# BigTimeMain.net
KiCad netlist of a schematic drawn in EAGLE
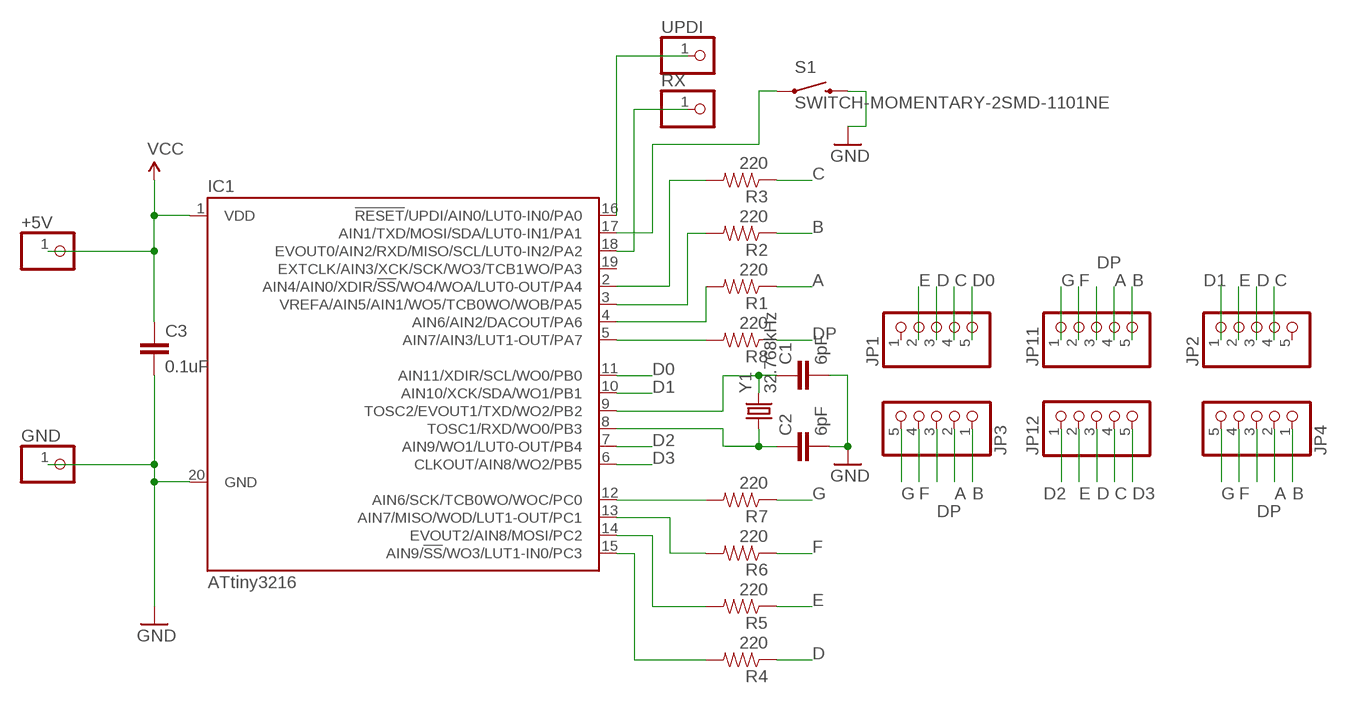
[diagram p0: schematic, sheet 1]

(export (version "E")
  (design (tool "Eeschema 10.0.6"))
  (components
    (comp (ref "+5V")
      (value "PINHD-1X1")
      (footprint "eagle-import:1X01")
      (libsource (lib "eagle-import") (part "PINHD-1X1"))
    )
    (comp (ref "C1")
      (value "6pF")
      (footprint "eagle-import:0805")
      (libsource (lib "eagle-import") (part "CAP0805"))
    )
    (comp (ref "C2")
      (value "6pF")
      (footprint "eagle-import:0805")
      (libsource (lib "eagle-import") (part "CAP0805"))
    )
    (comp (ref "C3")
      (value "0.1uF")
      (footprint "eagle-import:0805")
      (libsource (lib "eagle-import") (part "CAP0805"))
    )
    (comp (ref "GND")
      (value "PINHD-1X1")
      (footprint "eagle-import:1X01")
      (libsource (lib "eagle-import") (part "PINHD-1X1"))
    )
    (comp (ref "IC1")
      (value "ATtiny3216")
      (footprint "eagle-import:SOIC300")
      (fields (field (name "PARTNUM") "ATtiny3216-S*"))
      (libsource (lib "eagle-import") (part "ATTINY1616/3216-S"))
    )
    (comp (ref "JP1")
      (value "HEADER-1X576MIL")
      (footprint "eagle-import:1X05_ROUND_76")
      (libsource (lib "eagle-import") (part "HEADER-1X576MIL"))
    )
    (comp (ref "JP2")
      (value "HEADER-1X576MIL")
      (footprint "eagle-import:1X05_ROUND_76")
      (libsource (lib "eagle-import") (part "HEADER-1X576MIL"))
    )
    (comp (ref "JP3")
      (value "HEADER-1X576MIL")
      (footprint "eagle-import:1X05_ROUND_76")
      (libsource (lib "eagle-import") (part "HEADER-1X576MIL"))
    )
    (comp (ref "JP4")
      (value "HEADER-1X576MIL")
      (footprint "eagle-import:1X05_ROUND_76")
      (libsource (lib "eagle-import") (part "HEADER-1X576MIL"))
    )
    (comp (ref "JP11")
      (value "HEADER-1X576MIL")
      (footprint "eagle-import:1X05_ROUND_76")
      (libsource (lib "eagle-import") (part "HEADER-1X576MIL"))
    )
    (comp (ref "JP12")
      (value "HEADER-1X576MIL")
      (footprint "eagle-import:1X05_ROUND_76")
      (libsource (lib "eagle-import") (part "HEADER-1X576MIL"))
    )
    (comp (ref "R1")
      (value "220")
      (footprint "eagle-import:0805")
      (libsource (lib "eagle-import") (part "0.3OHM-1/8W-1%(0805)"))
    )
    (comp (ref "R2")
      (value "220")
      (footprint "eagle-import:0805")
      (libsource (lib "eagle-import") (part "0.3OHM-1/8W-1%(0805)"))
    )
    (comp (ref "R3")
      (value "220")
      (footprint "eagle-import:0805")
      (libsource (lib "eagle-import") (part "0.3OHM-1/8W-1%(0805)"))
    )
    (comp (ref "R4")
      (value "220")
      (footprint "eagle-import:0805")
      (libsource (lib "eagle-import") (part "0.3OHM-1/8W-1%(0805)"))
    )
    (comp (ref "R5")
      (value "220")
      (footprint "eagle-import:0805")
      (libsource (lib "eagle-import") (part "0.3OHM-1/8W-1%(0805)"))
    )
    (comp (ref "R6")
      (value "220")
      (footprint "eagle-import:0805")
      (libsource (lib "eagle-import") (part "0.3OHM-1/8W-1%(0805)"))
    )
    (comp (ref "R7")
      (value "220")
      (footprint "eagle-import:0805")
      (libsource (lib "eagle-import") (part "0.3OHM-1/8W-1%(0805)"))
    )
    (comp (ref "R8")
      (value "220")
      (footprint "eagle-import:0805")
      (libsource (lib "eagle-import") (part "0.3OHM-1/8W-1%(0805)"))
    )
    (comp (ref "RX")
      (value "PINHD-1X1")
      (footprint "eagle-import:1X01")
      (libsource (lib "eagle-import") (part "PINHD-1X1"))
    )
    (comp (ref "S1")
      (value "SWITCH-MOMENTARY-2SMD-1101NE")
      (footprint "eagle-import:TACTILE-SWITCH-1101NE")
      (libsource (lib "eagle-import") (part "SWITCH-MOMENTARY-2SMD-1101NE"))
    )
    (comp (ref "UPDI")
      (value "PINHD-1X1")
      (footprint "eagle-import:1X01")
      (libsource (lib "eagle-import") (part "PINHD-1X1"))
    )
    (comp (ref "Y1")
      (value "32.768kHz")
      (footprint "eagle-import:CRYSTAL-SMD-3.2X1.5MM")
      (libsource (lib "eagle-import") (part "CRYSTAL3.2X1.5MM"))
    )
  )
  (nets
    (net (code "1") (name "/A") (class "Default")
      (node (ref "JP11") (pin "4") (pinfunction "4_4") (pintype "passive"))
      (node (ref "JP3") (pin "2") (pinfunction "2_2") (pintype "passive"))
      (node (ref "JP4") (pin "2") (pinfunction "2_2") (pintype "passive"))
      (node (ref "R1") (pin "1") (pinfunction "1_1") (pintype "passive"))
    )
    (net (code "2") (name "/B") (class "Default")
      (node (ref "JP11") (pin "5") (pinfunction "5_5") (pintype "passive"))
      (node (ref "JP3") (pin "1") (pinfunction "1_1") (pintype "passive"))
      (node (ref "JP4") (pin "1") (pinfunction "1_1") (pintype "passive"))
      (node (ref "R2") (pin "1") (pinfunction "1_1") (pintype "passive"))
    )
    (net (code "3") (name "/C") (class "Default")
      (node (ref "JP1") (pin "4") (pinfunction "4_4") (pintype "passive"))
      (node (ref "JP12") (pin "4") (pinfunction "4_4") (pintype "passive"))
      (node (ref "JP2") (pin "4") (pinfunction "4_4") (pintype "passive"))
      (node (ref "R3") (pin "1") (pinfunction "1_1") (pintype "passive"))
    )
    (net (code "4") (name "/D") (class "Default")
      (node (ref "JP1") (pin "3") (pinfunction "3_3") (pintype "passive"))
      (node (ref "JP12") (pin "3") (pinfunction "3_3") (pintype "passive"))
      (node (ref "JP2") (pin "3") (pinfunction "3_3") (pintype "passive"))
      (node (ref "R4") (pin "1") (pinfunction "1_1") (pintype "passive"))
    )
    (net (code "5") (name "/D0") (class "Default")
      (node (ref "IC1") (pin "11") (pinfunction "AIN11/XDIR/SCL/WO0/PB0_11") (pintype "passive"))
      (node (ref "JP1") (pin "5") (pinfunction "5_5") (pintype "passive"))
    )
    (net (code "6") (name "/D1") (class "Default")
      (node (ref "IC1") (pin "10") (pinfunction "AIN10/XCK/SDA/WO1/PB1_10") (pintype "passive"))
      (node (ref "JP2") (pin "1") (pinfunction "1_1") (pintype "passive"))
    )
    (net (code "7") (name "/D2") (class "Default")
      (node (ref "IC1") (pin "7") (pinfunction "AIN9/WO1/LUT0-OUT/PB4_7") (pintype "passive"))
      (node (ref "JP12") (pin "1") (pinfunction "1_1") (pintype "passive"))
    )
    (net (code "8") (name "/D3") (class "Default")
      (node (ref "IC1") (pin "6") (pinfunction "CLKOUT/AIN8/WO2/PB5_6") (pintype "passive"))
      (node (ref "JP12") (pin "5") (pinfunction "5_5") (pintype "passive"))
    )
    (net (code "9") (name "/DP") (class "Default")
      (node (ref "JP11") (pin "3") (pinfunction "3_3") (pintype "passive"))
      (node (ref "JP3") (pin "3") (pinfunction "3_3") (pintype "passive"))
      (node (ref "JP4") (pin "3") (pinfunction "3_3") (pintype "passive"))
      (node (ref "R8") (pin "1") (pinfunction "1_1") (pintype "passive"))
    )
    (net (code "10") (name "/E") (class "Default")
      (node (ref "JP1") (pin "2") (pinfunction "2_2") (pintype "passive"))
      (node (ref "JP12") (pin "2") (pinfunction "2_2") (pintype "passive"))
      (node (ref "JP2") (pin "2") (pinfunction "2_2") (pintype "passive"))
      (node (ref "R5") (pin "1") (pinfunction "1_1") (pintype "passive"))
    )
    (net (code "11") (name "/F") (class "Default")
      (node (ref "JP11") (pin "2") (pinfunction "2_2") (pintype "passive"))
      (node (ref "JP3") (pin "4") (pinfunction "4_4") (pintype "passive"))
      (node (ref "JP4") (pin "4") (pinfunction "4_4") (pintype "passive"))
      (node (ref "R6") (pin "1") (pinfunction "1_1") (pintype "passive"))
    )
    (net (code "12") (name "/G") (class "Default")
      (node (ref "JP11") (pin "1") (pinfunction "1_1") (pintype "passive"))
      (node (ref "JP3") (pin "5") (pinfunction "5_5") (pintype "passive"))
      (node (ref "JP4") (pin "5") (pinfunction "5_5") (pintype "passive"))
      (node (ref "R7") (pin "1") (pinfunction "1_1") (pintype "passive"))
    )
    (net (code "13") (name "GND") (class "Default")
      (node (ref "C1") (pin "2") (pinfunction "2_2") (pintype "passive"))
      (node (ref "C2") (pin "2") (pinfunction "2_2") (pintype "passive"))
      (node (ref "C3") (pin "2") (pinfunction "2_2") (pintype "passive"))
      (node (ref "GND") (pin "1") (pinfunction "1_1") (pintype "passive"))
      (node (ref "IC1") (pin "20") (pinfunction "GND_20") (pintype "passive"))
      (node (ref "S1") (pin "2") (pinfunction "2_2") (pintype "passive"))
    )
    (net (code "14") (name "Net-(IC1-AIN1{slash}TXD{slash}MOSI{slash}SDA{slash}LUT0-IN1{slash}PA1)") (class "Default")
      (node (ref "IC1") (pin "17") (pinfunction "AIN1/TXD/MOSI/SDA/LUT0-IN1/PA1_17") (pintype "passive"))
      (node (ref "S1") (pin "1") (pinfunction "1_1") (pintype "passive"))
    )
    (net (code "15") (name "Net-(IC1-AIN4{slash}AIN0{slash}XDIR{slash}~{SS}{slash}WO4{slash}WOA{slash}LUT0-OUT{slash}PA4)") (class "Default")
      (node (ref "IC1") (pin "2") (pinfunction "AIN4/AIN0/XDIR/~{SS}/WO4/WOA/LUT0-OUT/PA4_2") (pintype "passive"))
      (node (ref "R3") (pin "2") (pinfunction "2_2") (pintype "passive"))
    )
    (net (code "16") (name "Net-(IC1-AIN6{slash}AIN2{slash}DACOUT{slash}PA6)") (class "Default")
      (node (ref "IC1") (pin "4") (pinfunction "AIN6/AIN2/DACOUT/PA6_4") (pintype "passive"))
      (node (ref "R1") (pin "2") (pinfunction "2_2") (pintype "passive"))
    )
    (net (code "17") (name "Net-(IC1-AIN6{slash}SCK{slash}TCB0WO{slash}WOC{slash}PC0)") (class "Default")
      (node (ref "IC1") (pin "12") (pinfunction "AIN6/SCK/TCB0WO/WOC/PC0_12") (pintype "passive"))
      (node (ref "R7") (pin "2") (pinfunction "2_2") (pintype "passive"))
    )
    (net (code "18") (name "Net-(IC1-AIN7{slash}AIN3{slash}LUT1-OUT{slash}PA7)") (class "Default")
      (node (ref "IC1") (pin "5") (pinfunction "AIN7/AIN3/LUT1-OUT/PA7_5") (pintype "passive"))
      (node (ref "R8") (pin "2") (pinfunction "2_2") (pintype "passive"))
    )
    (net (code "19") (name "Net-(IC1-AIN7{slash}MISO{slash}WOD{slash}LUT1-OUT{slash}PC1)") (class "Default")
      (node (ref "IC1") (pin "13") (pinfunction "AIN7/MISO/WOD/LUT1-OUT/PC1_13") (pintype "passive"))
      (node (ref "R6") (pin "2") (pinfunction "2_2") (pintype "passive"))
    )
    (net (code "20") (name "Net-(IC1-AIN9{slash}~{SS}{slash}WO3{slash}LUT1-IN0{slash}PC3)") (class "Default")
      (node (ref "IC1") (pin "15") (pinfunction "AIN9/~{SS}/WO3/LUT1-IN0/PC3_15") (pintype "passive"))
      (node (ref "R4") (pin "2") (pinfunction "2_2") (pintype "passive"))
    )
    (net (code "21") (name "Net-(IC1-EVOUT0{slash}AIN2{slash}RXD{slash}MISO{slash}SCL{slash}LUT0-IN2{slash}PA2)") (class "Default")
      (node (ref "IC1") (pin "18") (pinfunction "EVOUT0/AIN2/RXD/MISO/SCL/LUT0-IN2/PA2_18") (pintype "passive"))
      (node (ref "RX") (pin "1") (pinfunction "1_1") (pintype "passive"))
    )
    (net (code "22") (name "Net-(IC1-EVOUT2{slash}AIN8{slash}MOSI{slash}PC2)") (class "Default")
      (node (ref "IC1") (pin "14") (pinfunction "EVOUT2/AIN8/MOSI/PC2_14") (pintype "passive"))
      (node (ref "R5") (pin "2") (pinfunction "2_2") (pintype "passive"))
    )
    (net (code "23") (name "Net-(IC1-TOSC1{slash}RXD{slash}WO0{slash}PB3)") (class "Default")
      (node (ref "C2") (pin "1") (pinfunction "1_1") (pintype "passive"))
      (node (ref "IC1") (pin "8") (pinfunction "TOSC1/RXD/WO0/PB3_8") (pintype "passive"))
      (node (ref "Y1") (pin "P$1") (pinfunction "1_P$1") (pintype "passive"))
    )
    (net (code "24") (name "Net-(IC1-TOSC2{slash}EVOUT1{slash}TXD{slash}WO2{slash}PB2)") (class "Default")
      (node (ref "C1") (pin "1") (pinfunction "1_1") (pintype "passive"))
      (node (ref "IC1") (pin "9") (pinfunction "TOSC2/EVOUT1/TXD/WO2/PB2_9") (pintype "passive"))
      (node (ref "Y1") (pin "P$2") (pinfunction "2_P$2") (pintype "passive"))
    )
    (net (code "25") (name "Net-(IC1-VREFA{slash}AIN5{slash}AIN1{slash}WO5{slash}TCB0WO{slash}WOB{slash}PA5)") (class "Default")
      (node (ref "IC1") (pin "3") (pinfunction "VREFA/AIN5/AIN1/WO5/TCB0WO/WOB/PA5_3") (pintype "passive"))
      (node (ref "R2") (pin "2") (pinfunction "2_2") (pintype "passive"))
    )
    (net (code "26") (name "Net-(IC1-~{RESET}{slash}UPDI{slash}AIN0{slash}LUT0-IN0{slash}PA0)") (class "Default")
      (node (ref "IC1") (pin "16") (pinfunction "~{RESET}/UPDI/AIN0/LUT0-IN0/PA0_16") (pintype "passive"))
      (node (ref "UPDI") (pin "1") (pinfunction "1_1") (pintype "passive"))
    )
    (net (code "27") (name "VCC") (class "Default")
      (node (ref "+5V") (pin "1") (pinfunction "1_1") (pintype "passive"))
      (node (ref "C3") (pin "1") (pinfunction "1_1") (pintype "passive"))
      (node (ref "IC1") (pin "1") (pinfunction "VDD_1") (pintype "passive"))
    )
    (net (code "28") (name "unconnected-(IC1-EXTCLK{slash}AIN3{slash}XCK{slash}SCK{slash}WO3{slash}TCB1WO{slash}PA3-Pad19)") (class "Default")
      (node (ref "IC1") (pin "19") (pinfunction "EXTCLK/AIN3/XCK/SCK/WO3/TCB1WO/PA3_19") (pintype "passive"))
    )
    (net (code "29") (name "unconnected-(JP1-Pad1)") (class "Default")
      (node (ref "JP1") (pin "1") (pinfunction "1_1") (pintype "passive"))
    )
    (net (code "30") (name "unconnected-(JP2-Pad5)") (class "Default")
      (node (ref "JP2") (pin "5") (pinfunction "5_5") (pintype "passive"))
    )
  )
)
